# murdock_mcu_v3.net
KiCad netlist of a schematic drawn in EAGLE
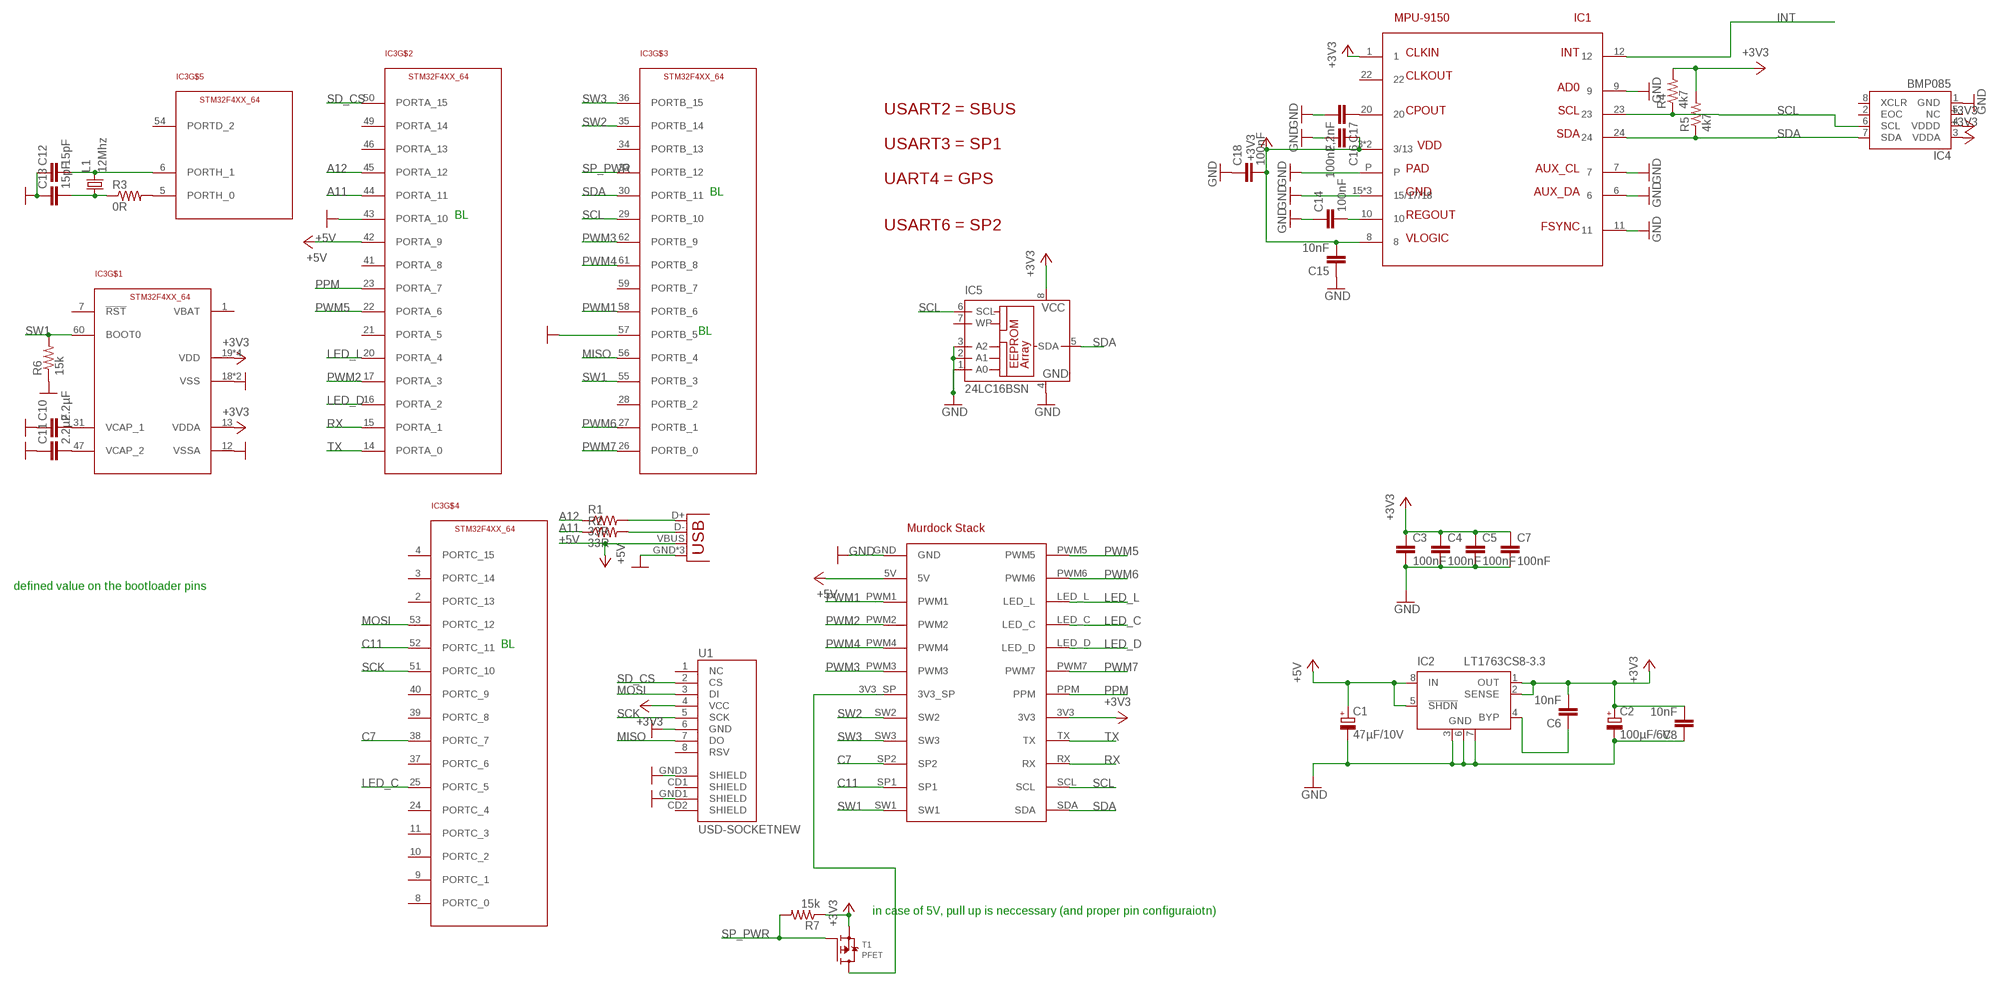
[diagram p0: schematic, sheet 1]

(export (version "E")
  (design (tool "Eeschema 10.0.6"))
  (components
    (comp (ref "C1")
      (value "47µF/10V")
      (footprint "eagle-import:SMC_C")
      (libsource (lib "eagle-import") (part "CPOL-EUSMCC"))
    )
    (comp (ref "C2")
      (value "100µF/6V")
      (footprint "eagle-import:SMC_C")
      (libsource (lib "eagle-import") (part "CPOL-EUSMCC"))
    )
    (comp (ref "C3")
      (value "100nF")
      (footprint "eagle-import:0402-CAP")
      (libsource (lib "eagle-import") (part "SparkFun-Capacitors_CAP0402-CAP"))
    )
    (comp (ref "C4")
      (value "100nF")
      (footprint "eagle-import:0402-CAP")
      (libsource (lib "eagle-import") (part "SparkFun-Capacitors_CAP0402-CAP"))
    )
    (comp (ref "C5")
      (value "100nF")
      (footprint "eagle-import:0402-CAP")
      (libsource (lib "eagle-import") (part "SparkFun-Capacitors_CAP0402-CAP"))
    )
    (comp (ref "C6")
      (value "10nF")
      (footprint "eagle-import:C0402")
      (libsource (lib "eagle-import") (part "C-EUC0402"))
    )
    (comp (ref "C7")
      (value "100nF")
      (footprint "eagle-import:0402-CAP")
      (libsource (lib "eagle-import") (part "SparkFun-Capacitors_CAP0402-CAP"))
    )
    (comp (ref "C8")
      (value "10nF")
      (footprint "eagle-import:C0402")
      (libsource (lib "eagle-import") (part "C-EUC0402"))
    )
    (comp (ref "C10")
      (value "2.2µF")
      (footprint "eagle-import:0805")
      (libsource (lib "eagle-import") (part "SparkFun-Capacitors_CAP0805"))
    )
    (comp (ref "C11")
      (value "2.2µF")
      (footprint "eagle-import:0805")
      (libsource (lib "eagle-import") (part "SparkFun-Capacitors_CAP0805"))
    )
    (comp (ref "C12")
      (value "15pF")
      (footprint "eagle-import:0402-CAP")
      (libsource (lib "eagle-import") (part "SparkFun-Capacitors_CAP0402-CAP"))
    )
    (comp (ref "C13")
      (value "15pF")
      (footprint "eagle-import:0402-CAP")
      (libsource (lib "eagle-import") (part "SparkFun-Capacitors_CAP0402-CAP"))
    )
    (comp (ref "C14")
      (value "100nF")
      (footprint "eagle-import:0402-CAP")
      (libsource (lib "eagle-import") (part "CAP0402-CAP"))
    )
    (comp (ref "C15")
      (value "10nF")
      (footprint "eagle-import:0402-CAP")
      (libsource (lib "eagle-import") (part "CAP0402-CAP"))
    )
    (comp (ref "C16")
      (value "100nF")
      (footprint "eagle-import:0402-CAP")
      (libsource (lib "eagle-import") (part "CAP0402-CAP"))
    )
    (comp (ref "C17")
      (value "2,2nF")
      (footprint "eagle-import:0402-CAP")
      (libsource (lib "eagle-import") (part "CAP0402-CAP"))
    )
    (comp (ref "C18")
      (value "100nF")
      (footprint "eagle-import:0402-CAP")
      (libsource (lib "eagle-import") (part "CAP0402-CAP"))
    )
    (comp (ref "IC1")
      (value "MPU-9150")
      (footprint "eagle-import:QFN24")
      (libsource (lib "eagle-import") (part "MPU-9150"))
    )
    (comp (ref "IC2")
      (value "LT1763CS8-3.3")
      (footprint "eagle-import:SOIC8")
      (libsource (lib "eagle-import") (part "LT1763CS8-3.3"))
    )
    (comp (ref "IC3")
      (value "STM32F4XX_64")
      (footprint "eagle-import:TQFP64")
      (libsource (lib "eagle-import") (part "STM32F4XX_64"))
    )
    (comp (ref "IC4")
      (value "BMP085")
      (footprint "eagle-import:BMP085")
      (libsource (lib "eagle-import") (part "BMP085"))
    )
    (comp (ref "IC5")
      (value "24LC16BSN")
      (footprint "eagle-import:SO-08")
      (fields (field (name "MF") "MICROCHIP") (field (name "MPN") "24LC16B/SN"))
      (libsource (lib "eagle-import") (part "24SNLC16B"))
    )
    (comp (ref "JP1")
      (value "USB-MICROB")
      (footprint "eagle-import:USB-MICROB")
      (libsource (lib "eagle-import") (part "USB-MICROB"))
    )
    (comp (ref "L1")
      (value "12Mhz")
      (footprint "eagle-import:X22")
      (libsource (lib "eagle-import") (part "X22-OSCILLATOR"))
    )
    (comp (ref "R1")
      (value "33R")
      (footprint "eagle-import:0402-RES")
      (libsource (lib "eagle-import") (part "SparkFun-Resistors_RESISTOR0402-RES"))
    )
    (comp (ref "R2")
      (value "33R")
      (footprint "eagle-import:0402-RES")
      (libsource (lib "eagle-import") (part "SparkFun-Resistors_RESISTOR0402-RES"))
    )
    (comp (ref "R3")
      (value "0R")
      (footprint "eagle-import:0402-RES")
      (libsource (lib "eagle-import") (part "SparkFun-Resistors_RESISTOR0402-RES"))
    )
    (comp (ref "R4")
      (value "4k7")
      (footprint "eagle-import:0402-RES")
      (libsource (lib "eagle-import") (part "RESISTOR0402-RES"))
    )
    (comp (ref "R5")
      (value "4k7")
      (footprint "eagle-import:0402-RES")
      (libsource (lib "eagle-import") (part "RESISTOR0402-RES"))
    )
    (comp (ref "R6")
      (value "15k")
      (footprint "eagle-import:0402-RES")
      (libsource (lib "eagle-import") (part "RESISTOR0402-RES"))
    )
    (comp (ref "R7")
      (value "15k")
      (footprint "eagle-import:0402-RES")
      (libsource (lib "eagle-import") (part "SparkFun-Resistors_RESISTOR0402-RES"))
    )
    (comp (ref "T1")
      (value "PFET")
      (footprint "eagle-import:SOT23-R")
      (libsource (lib "eagle-import") (part "MOSFET-P"))
    )
    (comp (ref "U1")
      (value "USD-SOCKETNEW")
      (footprint "eagle-import:MICRO-SD-SOCKET-PP")
      (libsource (lib "eagle-import") (part "USD-SOCKETNEW"))
    )
    (comp (ref "X2")
      (value "MURDOCK_STACK")
      (footprint "eagle-import:MURDOCK_STACK")
      (libsource (lib "eagle-import") (part "MURDOCK_STACK"))
    )
  )
  (nets
    (net (code "1") (name "+3V3") (class "Default")
      (node (ref "C15") (pin "2") (pinfunction "2_2") (pintype "passive"))
      (node (ref "C16") (pin "1") (pinfunction "1_1") (pintype "passive"))
      (node (ref "C18") (pin "2") (pinfunction "2_2") (pintype "passive"))
      (node (ref "C2") (pin "+") (pinfunction "+_+") (pintype "passive"))
      (node (ref "C3") (pin "1") (pinfunction "1_1") (pintype "passive"))
      (node (ref "C4") (pin "1") (pinfunction "1_1") (pintype "passive"))
      (node (ref "C5") (pin "1") (pinfunction "1_1") (pintype "passive"))
      (node (ref "C6") (pin "2") (pinfunction "2_2") (pintype "passive"))
      (node (ref "C7") (pin "1") (pinfunction "1_1") (pintype "passive"))
      (node (ref "C8") (pin "2") (pinfunction "2_2") (pintype "passive"))
      (node (ref "IC1") (pin "1") (pinfunction "1_1") (pintype "bidirectional"))
      (node (ref "IC1") (pin "13") (pinfunction "3/13_13") (pintype "bidirectional"))
      (node (ref "IC1") (pin "3") (pinfunction "3/13_3") (pintype "bidirectional"))
      (node (ref "IC1") (pin "8") (pinfunction "8_8") (pintype "bidirectional"))
      (node (ref "IC2") (pin "1") (pinfunction "OUT_1") (pintype "passive"))
      (node (ref "IC2") (pin "2") (pinfunction "SENSE_2") (pintype "input"))
      (node (ref "IC3") (pin "13") (pinfunction "VDDA_13") (pintype "bidirectional"))
      (node (ref "IC3") (pin "19") (pinfunction "VDD_19") (pintype "bidirectional"))
      (node (ref "IC3") (pin "32") (pinfunction "VDD_32") (pintype "bidirectional"))
      (node (ref "IC3") (pin "48") (pinfunction "VDD_48") (pintype "bidirectional"))
      (node (ref "IC3") (pin "64") (pinfunction "VDD_64") (pintype "bidirectional"))
      (node (ref "IC4") (pin "3") (pinfunction "VDDA_3") (pintype "power_in"))
      (node (ref "IC4") (pin "4") (pinfunction "VDDD_4") (pintype "power_in"))
      (node (ref "IC5") (pin "8") (pinfunction "VCC_8") (pintype "power_in"))
      (node (ref "R4") (pin "2") (pinfunction "2_2") (pintype "passive"))
      (node (ref "R5") (pin "2") (pinfunction "2_2") (pintype "passive"))
      (node (ref "R7") (pin "1") (pinfunction "1_1") (pintype "passive"))
      (node (ref "T1") (pin "2") (pinfunction "S_2") (pintype "passive"))
      (node (ref "U1") (pin "4") (pinfunction "VCC_4") (pintype "bidirectional"))
      (node (ref "X2") (pin "3V3") (pinfunction "3V3_3V3") (pintype "bidirectional"))
    )
    (net (code "2") (name "+5V") (class "Default")
      (node (ref "C1") (pin "+") (pinfunction "+_+") (pintype "passive"))
      (node (ref "IC2") (pin "5") (pinfunction "~{SHDN}_5") (pintype "input"))
      (node (ref "IC2") (pin "8") (pinfunction "IN_8") (pintype "input"))
      (node (ref "IC3") (pin "42") (pinfunction "PORTA_9_42") (pintype "bidirectional"))
      (node (ref "JP1") (pin "VBUS") (pinfunction "VBUS_VBUS") (pintype "bidirectional"))
      (node (ref "X2") (pin "5V") (pinfunction "5V_5V") (pintype "bidirectional"))
    )
    (net (code "3") (name "/A11") (class "Default")
      (node (ref "IC3") (pin "44") (pinfunction "PORTA_11_44") (pintype "bidirectional"))
      (node (ref "R2") (pin "1") (pinfunction "1_1") (pintype "passive"))
    )
    (net (code "4") (name "/A12") (class "Default")
      (node (ref "IC3") (pin "45") (pinfunction "PORTA_12_45") (pintype "bidirectional"))
      (node (ref "R1") (pin "1") (pinfunction "1_1") (pintype "passive"))
    )
    (net (code "5") (name "/C7") (class "Default")
      (node (ref "IC3") (pin "38") (pinfunction "PORTC_7_38") (pintype "bidirectional"))
      (node (ref "X2") (pin "SP2") (pinfunction "SP2_SP2") (pintype "bidirectional"))
    )
    (net (code "6") (name "/C11") (class "Default")
      (node (ref "IC3") (pin "52") (pinfunction "PORTC_11_52") (pintype "bidirectional"))
      (node (ref "X2") (pin "SP1") (pinfunction "SP1_SP1") (pintype "bidirectional"))
    )
    (net (code "7") (name "/INT") (class "Default")
      (node (ref "IC1") (pin "12") (pinfunction "12_12") (pintype "bidirectional"))
    )
    (net (code "8") (name "/LED_C") (class "Default")
      (node (ref "IC3") (pin "25") (pinfunction "PORTC_5_25") (pintype "bidirectional"))
      (node (ref "X2") (pin "LED_C") (pinfunction "LED_C_LED_C") (pintype "bidirectional"))
    )
    (net (code "9") (name "/LED_D") (class "Default")
      (node (ref "IC3") (pin "16") (pinfunction "PORTA_2_16") (pintype "bidirectional"))
      (node (ref "X2") (pin "LED_D") (pinfunction "LED_D_LED_D") (pintype "bidirectional"))
    )
    (net (code "10") (name "/LED_L") (class "Default")
      (node (ref "IC3") (pin "20") (pinfunction "PORTA_4_20") (pintype "bidirectional"))
      (node (ref "X2") (pin "LED_L") (pinfunction "LED_L_LED_L") (pintype "bidirectional"))
    )
    (net (code "11") (name "/MISO") (class "Default")
      (node (ref "IC3") (pin "56") (pinfunction "PORTB_4_56") (pintype "bidirectional"))
      (node (ref "U1") (pin "7") (pinfunction "DO_7") (pintype "bidirectional"))
    )
    (net (code "12") (name "/MOSI") (class "Default")
      (node (ref "IC3") (pin "53") (pinfunction "PORTC_12_53") (pintype "bidirectional"))
      (node (ref "U1") (pin "3") (pinfunction "DI_3") (pintype "bidirectional"))
    )
    (net (code "13") (name "/PPM") (class "Default")
      (node (ref "IC3") (pin "23") (pinfunction "PORTA_7_23") (pintype "bidirectional"))
      (node (ref "X2") (pin "PPM") (pinfunction "PPM_PPM") (pintype "bidirectional"))
    )
    (net (code "14") (name "/PWM1") (class "Default")
      (node (ref "IC3") (pin "58") (pinfunction "PORTB_6_58") (pintype "bidirectional"))
      (node (ref "X2") (pin "PWM1") (pinfunction "PWM1_PWM1") (pintype "bidirectional"))
    )
    (net (code "15") (name "/PWM2") (class "Default")
      (node (ref "IC3") (pin "17") (pinfunction "PORTA_3_17") (pintype "bidirectional"))
      (node (ref "X2") (pin "PWM2") (pinfunction "PWM2_PWM2") (pintype "bidirectional"))
    )
    (net (code "16") (name "/PWM3") (class "Default")
      (node (ref "IC3") (pin "62") (pinfunction "PORTB_9_62") (pintype "bidirectional"))
      (node (ref "X2") (pin "PWM3") (pinfunction "PWM3_PWM3") (pintype "bidirectional"))
    )
    (net (code "17") (name "/PWM4") (class "Default")
      (node (ref "IC3") (pin "61") (pinfunction "PORTB_8_61") (pintype "bidirectional"))
      (node (ref "X2") (pin "PWM4") (pinfunction "PWM4_PWM4") (pintype "bidirectional"))
    )
    (net (code "18") (name "/PWM5") (class "Default")
      (node (ref "IC3") (pin "22") (pinfunction "PORTA_6_22") (pintype "bidirectional"))
      (node (ref "X2") (pin "PWM5") (pinfunction "PWM5_PWM5") (pintype "bidirectional"))
    )
    (net (code "19") (name "/PWM6") (class "Default")
      (node (ref "IC3") (pin "27") (pinfunction "PORTB_1_27") (pintype "bidirectional"))
      (node (ref "X2") (pin "PWM6") (pinfunction "PWM6_PWM6") (pintype "bidirectional"))
    )
    (net (code "20") (name "/PWM7") (class "Default")
      (node (ref "IC3") (pin "26") (pinfunction "PORTB_0_26") (pintype "bidirectional"))
      (node (ref "X2") (pin "PWM7") (pinfunction "PWM7_PWM7") (pintype "bidirectional"))
    )
    (net (code "21") (name "/RX") (class "Default")
      (node (ref "IC3") (pin "15") (pinfunction "PORTA_1_15") (pintype "bidirectional"))
      (node (ref "X2") (pin "RX") (pinfunction "RX_RX") (pintype "bidirectional"))
    )
    (net (code "22") (name "/SCK") (class "Default")
      (node (ref "IC3") (pin "51") (pinfunction "PORTC_10_51") (pintype "bidirectional"))
      (node (ref "U1") (pin "5") (pinfunction "SCK_5") (pintype "bidirectional"))
    )
    (net (code "23") (name "/SCL") (class "Default")
      (node (ref "IC1") (pin "23") (pinfunction "23_23") (pintype "bidirectional"))
      (node (ref "IC3") (pin "29") (pinfunction "PORTB_10_29") (pintype "bidirectional"))
      (node (ref "IC4") (pin "6") (pinfunction "SCL_6") (pintype "input"))
      (node (ref "IC5") (pin "6") (pinfunction "SCL_6") (pintype "input"))
      (node (ref "R4") (pin "1") (pinfunction "1_1") (pintype "passive"))
      (node (ref "X2") (pin "SCL") (pinfunction "SCL_SCL") (pintype "bidirectional"))
    )
    (net (code "24") (name "/SDA") (class "Default")
      (node (ref "IC1") (pin "24") (pinfunction "24_24") (pintype "bidirectional"))
      (node (ref "IC3") (pin "30") (pinfunction "PORTB_11_30") (pintype "bidirectional"))
      (node (ref "IC4") (pin "7") (pinfunction "SDA_7") (pintype "bidirectional"))
      (node (ref "IC5") (pin "5") (pinfunction "SDA_5") (pintype "bidirectional"))
      (node (ref "R5") (pin "1") (pinfunction "1_1") (pintype "passive"))
      (node (ref "X2") (pin "SDA") (pinfunction "SDA_SDA") (pintype "bidirectional"))
    )
    (net (code "25") (name "/SD_CS") (class "Default")
      (node (ref "IC3") (pin "50") (pinfunction "PORTA_15_50") (pintype "bidirectional"))
      (node (ref "U1") (pin "2") (pinfunction "CS_2") (pintype "bidirectional"))
    )
    (net (code "26") (name "/SP_PWR") (class "Default")
      (node (ref "IC3") (pin "33") (pinfunction "PORTB_12_33") (pintype "bidirectional"))
      (node (ref "R7") (pin "2") (pinfunction "2_2") (pintype "passive"))
      (node (ref "T1") (pin "1") (pinfunction "G_1") (pintype "passive"))
    )
    (net (code "27") (name "/SW1") (class "Default")
      (node (ref "IC3") (pin "55") (pinfunction "PORTB_3_55") (pintype "bidirectional"))
      (node (ref "IC3") (pin "60") (pinfunction "BOOT0_60") (pintype "bidirectional"))
      (node (ref "R6") (pin "2") (pinfunction "2_2") (pintype "passive"))
      (node (ref "X2") (pin "SW1") (pinfunction "SW1_SW1") (pintype "bidirectional"))
    )
    (net (code "28") (name "/SW2") (class "Default")
      (node (ref "IC3") (pin "35") (pinfunction "PORTB_14_35") (pintype "bidirectional"))
      (node (ref "X2") (pin "SW2") (pinfunction "SW2_SW2") (pintype "bidirectional"))
    )
    (net (code "29") (name "/SW3") (class "Default")
      (node (ref "IC3") (pin "36") (pinfunction "PORTB_15_36") (pintype "bidirectional"))
      (node (ref "X2") (pin "SW3") (pinfunction "SW3_SW3") (pintype "bidirectional"))
    )
    (net (code "30") (name "/TX") (class "Default")
      (node (ref "IC3") (pin "14") (pinfunction "PORTA_0_14") (pintype "bidirectional"))
      (node (ref "X2") (pin "TX") (pinfunction "TX_TX") (pintype "bidirectional"))
    )
    (net (code "31") (name "GND") (class "Default")
      (node (ref "C1") (pin "-") (pinfunction "-_-") (pintype "passive"))
      (node (ref "C10") (pin "1") (pinfunction "1_1") (pintype "passive"))
      (node (ref "C11") (pin "1") (pinfunction "1_1") (pintype "passive"))
      (node (ref "C12") (pin "1") (pinfunction "1_1") (pintype "passive"))
      (node (ref "C13") (pin "1") (pinfunction "1_1") (pintype "passive"))
      (node (ref "C14") (pin "1") (pinfunction "1_1") (pintype "passive"))
      (node (ref "C15") (pin "1") (pinfunction "1_1") (pintype "passive"))
      (node (ref "C16") (pin "2") (pinfunction "2_2") (pintype "passive"))
      (node (ref "C17") (pin "2") (pinfunction "2_2") (pintype "passive"))
      (node (ref "C18") (pin "1") (pinfunction "1_1") (pintype "passive"))
      (node (ref "C2") (pin "-") (pinfunction "-_-") (pintype "passive"))
      (node (ref "C3") (pin "2") (pinfunction "2_2") (pintype "passive"))
      (node (ref "C4") (pin "2") (pinfunction "2_2") (pintype "passive"))
      (node (ref "C5") (pin "2") (pinfunction "2_2") (pintype "passive"))
      (node (ref "C7") (pin "2") (pinfunction "2_2") (pintype "passive"))
      (node (ref "C8") (pin "1") (pinfunction "1_1") (pintype "passive"))
      (node (ref "IC1") (pin "11") (pinfunction "11_11") (pintype "bidirectional"))
      (node (ref "IC1") (pin "15") (pinfunction "15/17/18_15") (pintype "bidirectional"))
      (node (ref "IC1") (pin "17") (pinfunction "15/17/18_17") (pintype "bidirectional"))
      (node (ref "IC1") (pin "18") (pinfunction "15/17/18_18") (pintype "bidirectional"))
      (node (ref "IC1") (pin "6") (pinfunction "6_6") (pintype "bidirectional"))
      (node (ref "IC1") (pin "7") (pinfunction "7_7") (pintype "bidirectional"))
      (node (ref "IC1") (pin "9") (pinfunction "9_9") (pintype "bidirectional"))
      (node (ref "IC1") (pin "P") (pinfunction "P_P") (pintype "bidirectional"))
      (node (ref "IC2") (pin "3") (pinfunction "GND_3") (pintype "power_in"))
      (node (ref "IC2") (pin "6") (pinfunction "GND_6") (pintype "power_in"))
      (node (ref "IC2") (pin "7") (pinfunction "GND_7") (pintype "power_in"))
      (node (ref "IC3") (pin "12") (pinfunction "VSSA_12") (pintype "bidirectional"))
      (node (ref "IC3") (pin "18") (pinfunction "VSS_18") (pintype "bidirectional"))
      (node (ref "IC3") (pin "43") (pinfunction "PORTA_10_43") (pintype "bidirectional"))
      (node (ref "IC3") (pin "57") (pinfunction "PORTB_5_57") (pintype "bidirectional"))
      (node (ref "IC3") (pin "63") (pinfunction "VSS_63") (pintype "bidirectional"))
      (node (ref "IC4") (pin "1") (pinfunction "GND_1") (pintype "power_in"))
      (node (ref "IC5") (pin "1") (pinfunction "A0_1") (pintype "input"))
      (node (ref "IC5") (pin "2") (pinfunction "A1_2") (pintype "input"))
      (node (ref "IC5") (pin "3") (pinfunction "A2_3") (pintype "input"))
      (node (ref "IC5") (pin "4") (pinfunction "GND_4") (pintype "power_in"))
      (node (ref "JP1") (pin "GND") (pinfunction "GND_GND") (pintype "bidirectional"))
      (node (ref "JP1") (pin "MT1") (pinfunction "GND_MT1") (pintype "bidirectional"))
      (node (ref "JP1") (pin "MT2") (pinfunction "GND_MT2") (pintype "bidirectional"))
      (node (ref "R6") (pin "1") (pinfunction "1_1") (pintype "passive"))
      (node (ref "U1") (pin "6") (pinfunction "GND_6") (pintype "bidirectional"))
      (node (ref "U1") (pin "GND1") (pinfunction "SHIELD_GND1") (pintype "bidirectional"))
      (node (ref "U1") (pin "GND3") (pinfunction "SHIELD_GND3") (pintype "bidirectional"))
      (node (ref "X2") (pin "GND") (pinfunction "GND_GND") (pintype "bidirectional"))
    )
    (net (code "32") (name "Net-(C13-Pad2)") (class "Default")
      (node (ref "C13") (pin "2") (pinfunction "2_2") (pintype "passive"))
      (node (ref "L1") (pin "1") (pinfunction "1_1") (pintype "passive"))
      (node (ref "R3") (pin "1") (pinfunction "1_1") (pintype "passive"))
    )
    (net (code "33") (name "Net-(C14-Pad2)") (class "Default")
      (node (ref "C14") (pin "2") (pinfunction "2_2") (pintype "passive"))
      (node (ref "IC1") (pin "10") (pinfunction "10_10") (pintype "bidirectional"))
    )
    (net (code "34") (name "Net-(C17-Pad1)") (class "Default")
      (node (ref "C17") (pin "1") (pinfunction "1_1") (pintype "passive"))
      (node (ref "IC1") (pin "20") (pinfunction "20_20") (pintype "bidirectional"))
    )
    (net (code "35") (name "Net-(IC2-BYP)") (class "Default")
      (node (ref "C6") (pin "1") (pinfunction "1_1") (pintype "passive"))
      (node (ref "IC2") (pin "4") (pinfunction "BYP_4") (pintype "input"))
    )
    (net (code "36") (name "Net-(IC3A-VCAP_1)") (class "Default")
      (node (ref "C10") (pin "2") (pinfunction "2_2") (pintype "passive"))
      (node (ref "IC3") (pin "31") (pinfunction "VCAP_1_31") (pintype "bidirectional"))
    )
    (net (code "37") (name "Net-(IC3A-VCAP_2)") (class "Default")
      (node (ref "C11") (pin "2") (pinfunction "2_2") (pintype "passive"))
      (node (ref "IC3") (pin "47") (pinfunction "VCAP_2_47") (pintype "bidirectional"))
    )
    (net (code "38") (name "Net-(IC3E-PORTH_0)") (class "Default")
      (node (ref "IC3") (pin "5") (pinfunction "PORTH_0_5") (pintype "bidirectional"))
      (node (ref "R3") (pin "2") (pinfunction "2_2") (pintype "passive"))
    )
    (net (code "39") (name "Net-(IC3E-PORTH_1)") (class "Default")
      (node (ref "C12") (pin "2") (pinfunction "2_2") (pintype "passive"))
      (node (ref "IC3") (pin "6") (pinfunction "PORTH_1_6") (pintype "bidirectional"))
      (node (ref "L1") (pin "3") (pinfunction "2_3") (pintype "passive"))
    )
    (net (code "40") (name "Net-(JP1-PadD+)") (class "Default")
      (node (ref "JP1") (pin "D+") (pinfunction "D+_D+") (pintype "bidirectional"))
      (node (ref "R1") (pin "2") (pinfunction "2_2") (pintype "passive"))
    )
    (net (code "41") (name "Net-(JP1-PadD-)") (class "Default")
      (node (ref "JP1") (pin "D-") (pinfunction "D-_D-") (pintype "bidirectional"))
      (node (ref "R2") (pin "2") (pinfunction "2_2") (pintype "passive"))
    )
    (net (code "42") (name "Net-(T1-D)") (class "Default")
      (node (ref "T1") (pin "3") (pinfunction "D_3") (pintype "passive"))
      (node (ref "X2") (pin "3V3_SP") (pinfunction "3V3_SP_3V3_SP") (pintype "bidirectional"))
    )
    (net (code "43") (name "unconnected-(IC1-Pad22)") (class "Default")
      (node (ref "IC1") (pin "22") (pinfunction "22_22") (pintype "bidirectional"))
    )
    (net (code "44") (name "unconnected-(IC3A-VBAT-Pad1)") (class "Default")
      (node (ref "IC3") (pin "1") (pinfunction "VBAT_1") (pintype "bidirectional"))
    )
    (net (code "45") (name "unconnected-(IC3A-~{RST}-Pad7)") (class "Default")
      (node (ref "IC3") (pin "7") (pinfunction "~{RST}_7") (pintype "bidirectional"))
    )
    (net (code "46") (name "unconnected-(IC3B-PORTA_5-Pad21)") (class "Default")
      (node (ref "IC3") (pin "21") (pinfunction "PORTA_5_21") (pintype "bidirectional"))
    )
    (net (code "47") (name "unconnected-(IC3B-PORTA_8-Pad41)") (class "Default")
      (node (ref "IC3") (pin "41") (pinfunction "PORTA_8_41") (pintype "bidirectional"))
    )
    (net (code "48") (name "unconnected-(IC3B-PORTA_13-Pad46)") (class "Default")
      (node (ref "IC3") (pin "46") (pinfunction "PORTA_13_46") (pintype "bidirectional"))
    )
    (net (code "49") (name "unconnected-(IC3B-PORTA_14-Pad49)") (class "Default")
      (node (ref "IC3") (pin "49") (pinfunction "PORTA_14_49") (pintype "bidirectional"))
    )
    (net (code "50") (name "unconnected-(IC3C-PORTB_2-Pad28)") (class "Default")
      (node (ref "IC3") (pin "28") (pinfunction "PORTB_2_28") (pintype "bidirectional"))
    )
    (net (code "51") (name "unconnected-(IC3C-PORTB_7-Pad59)") (class "Default")
      (node (ref "IC3") (pin "59") (pinfunction "PORTB_7_59") (pintype "bidirectional"))
    )
    (net (code "52") (name "unconnected-(IC3C-PORTB_13-Pad34)") (class "Default")
      (node (ref "IC3") (pin "34") (pinfunction "PORTB_13_34") (pintype "bidirectional"))
    )
    (net (code "53") (name "unconnected-(IC3D-PORTC_0-Pad8)") (class "Default")
      (node (ref "IC3") (pin "8") (pinfunction "PORTC_0_8") (pintype "bidirectional"))
    )
    (net (code "54") (name "unconnected-(IC3D-PORTC_1-Pad9)") (class "Default")
      (node (ref "IC3") (pin "9") (pinfunction "PORTC_1_9") (pintype "bidirectional"))
    )
    (net (code "55") (name "unconnected-(IC3D-PORTC_2-Pad10)") (class "Default")
      (node (ref "IC3") (pin "10") (pinfunction "PORTC_2_10") (pintype "bidirectional"))
    )
    (net (code "56") (name "unconnected-(IC3D-PORTC_3-Pad11)") (class "Default")
      (node (ref "IC3") (pin "11") (pinfunction "PORTC_3_11") (pintype "bidirectional"))
    )
    (net (code "57") (name "unconnected-(IC3D-PORTC_4-Pad24)") (class "Default")
      (node (ref "IC3") (pin "24") (pinfunction "PORTC_4_24") (pintype "bidirectional"))
    )
    (net (code "58") (name "unconnected-(IC3D-PORTC_6-Pad37)") (class "Default")
      (node (ref "IC3") (pin "37") (pinfunction "PORTC_6_37") (pintype "bidirectional"))
    )
    (net (code "59") (name "unconnected-(IC3D-PORTC_8-Pad39)") (class "Default")
      (node (ref "IC3") (pin "39") (pinfunction "PORTC_8_39") (pintype "bidirectional"))
    )
    (net (code "60") (name "unconnected-(IC3D-PORTC_9-Pad40)") (class "Default")
      (node (ref "IC3") (pin "40") (pinfunction "PORTC_9_40") (pintype "bidirectional"))
    )
    (net (code "61") (name "unconnected-(IC3D-PORTC_13-Pad2)") (class "Default")
      (node (ref "IC3") (pin "2") (pinfunction "PORTC_13_2") (pintype "bidirectional"))
    )
    (net (code "62") (name "unconnected-(IC3D-PORTC_14-Pad3)") (class "Default")
      (node (ref "IC3") (pin "3") (pinfunction "PORTC_14_3") (pintype "bidirectional"))
    )
    (net (code "63") (name "unconnected-(IC3D-PORTC_15-Pad4)") (class "Default")
      (node (ref "IC3") (pin "4") (pinfunction "PORTC_15_4") (pintype "bidirectional"))
    )
    (net (code "64") (name "unconnected-(IC3E-PORTD_2-Pad54)") (class "Default")
      (node (ref "IC3") (pin "54") (pinfunction "PORTD_2_54") (pintype "bidirectional"))
    )
    (net (code "65") (name "unconnected-(IC4-EOC-Pad2)") (class "Default")
      (node (ref "IC4") (pin "2") (pinfunction "EOC_2") (pintype "output"))
    )
    (net (code "66") (name "unconnected-(IC4-NC-Pad5)") (class "Default")
      (node (ref "IC4") (pin "5") (pinfunction "NC_5") (pintype "bidirectional"))
    )
    (net (code "67") (name "unconnected-(IC4-XCLR-Pad8)") (class "Default")
      (node (ref "IC4") (pin "8") (pinfunction "XCLR_8") (pintype "input"))
    )
    (net (code "68") (name "unconnected-(IC5-WP-Pad7)") (class "Default")
      (node (ref "IC5") (pin "7") (pinfunction "WP_7") (pintype "input"))
    )
    (net (code "69") (name "unconnected-(U1-NC-Pad1)") (class "Default")
      (node (ref "U1") (pin "1") (pinfunction "NC_1") (pintype "bidirectional"))
    )
    (net (code "70") (name "unconnected-(U1-RSV-Pad8)") (class "Default")
      (node (ref "U1") (pin "8") (pinfunction "RSV_8") (pintype "bidirectional"))
    )
    (net (code "71") (name "unconnected-(U1-SHIELD-PadCD1)") (class "Default")
      (node (ref "U1") (pin "CD1") (pinfunction "SHIELD_CD1") (pintype "bidirectional"))
    )
    (net (code "72") (name "unconnected-(U1-SHIELD-PadCD2)") (class "Default")
      (node (ref "U1") (pin "CD2") (pinfunction "SHIELD_CD2") (pintype "bidirectional"))
    )
  )
)
